# screen.net
KiCad netlist of a schematic drawn in Altium Designer
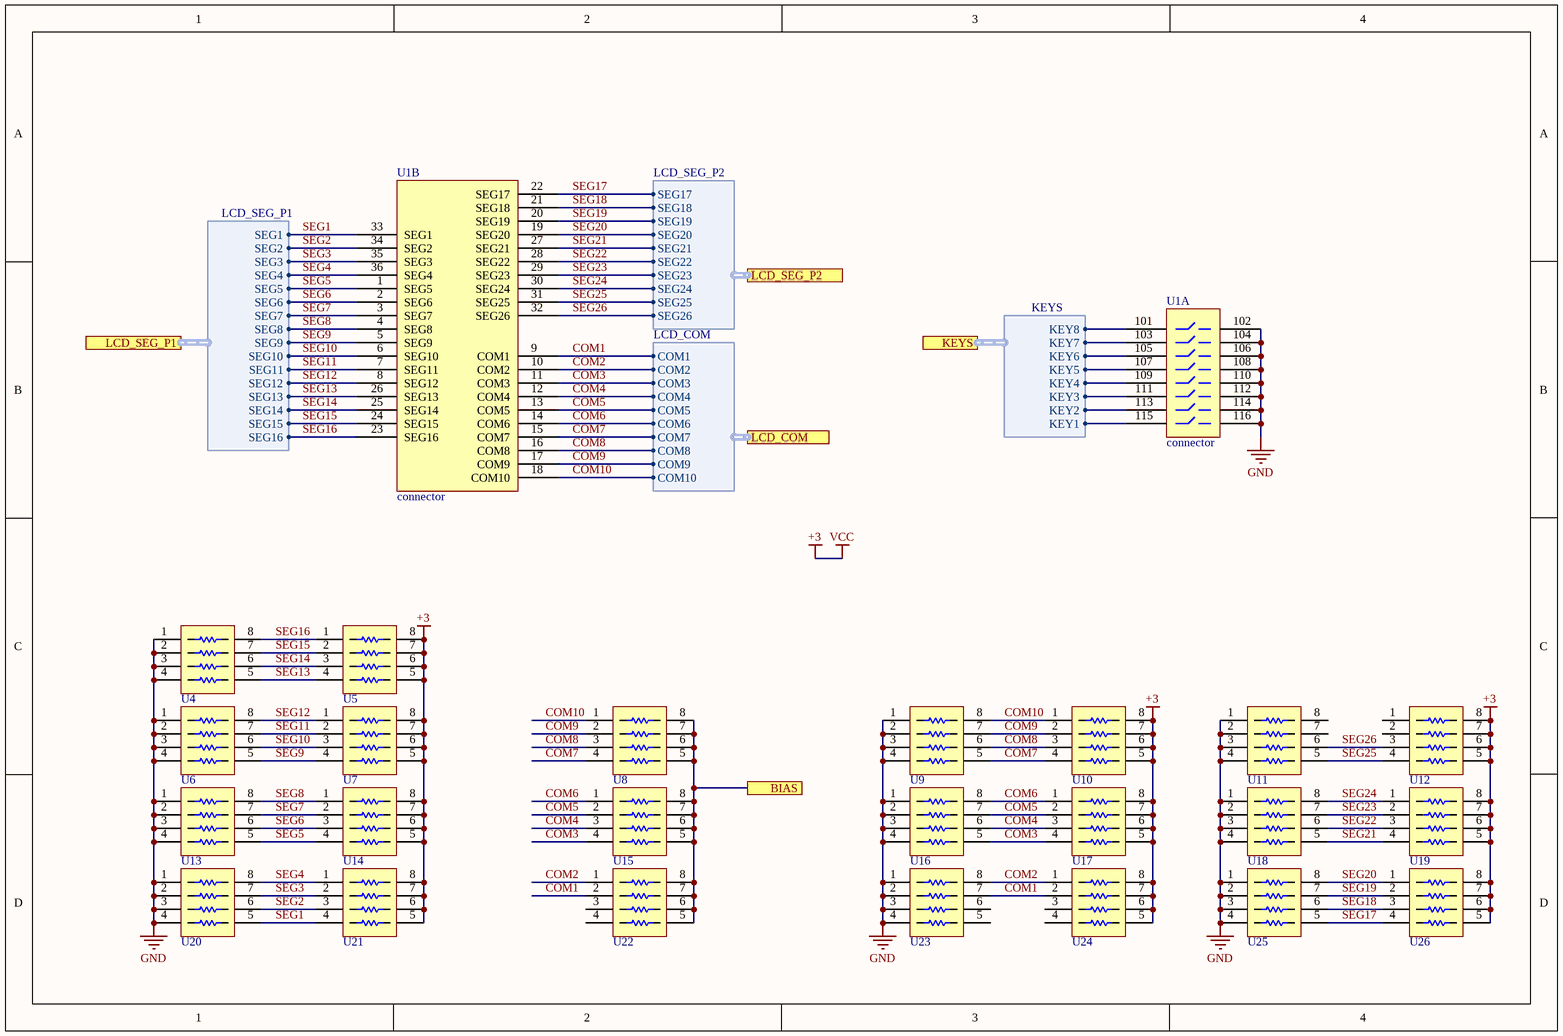
[diagram p0: screen.SchDoc]

(export (version "E")
  (design (tool "Eeschema 10.0.6"))
  (components
    (comp (ref "U1") (value "connector") (footprint "kunborad") (libsource (lib "cl_sch") (part "kunboard")))
    (comp (ref "U4")
      (value "RES_BATCH")
      (footprint "0603_RES_BATCH")
      (libsource (lib "cl_sch") (part "RES_BATCH"))
    )
    (comp (ref "U5")
      (value "RES_BATCH")
      (footprint "0603_RES_BATCH")
      (libsource (lib "cl_sch") (part "RES_BATCH"))
    )
    (comp (ref "U6")
      (value "RES_BATCH")
      (footprint "0603_RES_BATCH")
      (libsource (lib "cl_sch") (part "RES_BATCH"))
    )
    (comp (ref "U7")
      (value "RES_BATCH")
      (footprint "0603_RES_BATCH")
      (libsource (lib "cl_sch") (part "RES_BATCH"))
    )
    (comp (ref "U8")
      (value "RES_BATCH")
      (footprint "0603_RES_BATCH")
      (libsource (lib "cl_sch") (part "RES_BATCH"))
    )
    (comp (ref "U9")
      (value "RES_BATCH")
      (footprint "0603_RES_BATCH")
      (libsource (lib "cl_sch") (part "RES_BATCH"))
    )
    (comp (ref "U10")
      (value "RES_BATCH")
      (footprint "0603_RES_BATCH")
      (libsource (lib "cl_sch") (part "RES_BATCH"))
    )
    (comp (ref "U11")
      (value "RES_BATCH")
      (footprint "0603_RES_BATCH")
      (libsource (lib "cl_sch") (part "RES_BATCH"))
    )
    (comp (ref "U12")
      (value "RES_BATCH")
      (footprint "0603_RES_BATCH")
      (libsource (lib "cl_sch") (part "RES_BATCH"))
    )
    (comp (ref "U13")
      (value "RES_BATCH")
      (footprint "0603_RES_BATCH")
      (libsource (lib "cl_sch") (part "RES_BATCH"))
    )
    (comp (ref "U14")
      (value "RES_BATCH")
      (footprint "0603_RES_BATCH")
      (libsource (lib "cl_sch") (part "RES_BATCH"))
    )
    (comp (ref "U15")
      (value "RES_BATCH")
      (footprint "0603_RES_BATCH")
      (libsource (lib "cl_sch") (part "RES_BATCH"))
    )
    (comp (ref "U16")
      (value "RES_BATCH")
      (footprint "0603_RES_BATCH")
      (libsource (lib "cl_sch") (part "RES_BATCH"))
    )
    (comp (ref "U17")
      (value "RES_BATCH")
      (footprint "0603_RES_BATCH")
      (libsource (lib "cl_sch") (part "RES_BATCH"))
    )
    (comp (ref "U18")
      (value "RES_BATCH")
      (footprint "0603_RES_BATCH")
      (libsource (lib "cl_sch") (part "RES_BATCH"))
    )
    (comp (ref "U19")
      (value "RES_BATCH")
      (footprint "0603_RES_BATCH")
      (libsource (lib "cl_sch") (part "RES_BATCH"))
    )
    (comp (ref "U20")
      (value "RES_BATCH")
      (footprint "0603_RES_BATCH")
      (libsource (lib "cl_sch") (part "RES_BATCH"))
    )
    (comp (ref "U21")
      (value "RES_BATCH")
      (footprint "0603_RES_BATCH")
      (libsource (lib "cl_sch") (part "RES_BATCH"))
    )
    (comp (ref "U22")
      (value "RES_BATCH")
      (footprint "0603_RES_BATCH")
      (libsource (lib "cl_sch") (part "RES_BATCH"))
    )
    (comp (ref "U23")
      (value "RES_BATCH")
      (footprint "0603_RES_BATCH")
      (libsource (lib "cl_sch") (part "RES_BATCH"))
    )
    (comp (ref "U24")
      (value "RES_BATCH")
      (footprint "0603_RES_BATCH")
      (libsource (lib "cl_sch") (part "RES_BATCH"))
    )
    (comp (ref "U25")
      (value "RES_BATCH")
      (footprint "0603_RES_BATCH")
      (libsource (lib "cl_sch") (part "RES_BATCH"))
    )
    (comp (ref "U26")
      (value "RES_BATCH")
      (footprint "0603_RES_BATCH")
      (libsource (lib "cl_sch") (part "RES_BATCH"))
    )
  )
  (nets
    (net (code "5") (name "+3") (class "Default")
      (node (ref "U10") (pin "5") (pinfunction "5_5") (pintype "passive"))
      (node (ref "U10") (pin "6") (pinfunction "6_6") (pintype "passive"))
      (node (ref "U10") (pin "7") (pinfunction "7_7") (pintype "passive"))
      (node (ref "U10") (pin "8") (pinfunction "8_8") (pintype "passive"))
      (node (ref "U12") (pin "5") (pinfunction "5_5") (pintype "passive"))
      (node (ref "U12") (pin "6") (pinfunction "6_6") (pintype "passive"))
      (node (ref "U12") (pin "7") (pinfunction "7_7") (pintype "passive"))
      (node (ref "U12") (pin "8") (pinfunction "8_8") (pintype "passive"))
      (node (ref "U14") (pin "5") (pinfunction "5_5") (pintype "passive"))
      (node (ref "U14") (pin "6") (pinfunction "6_6") (pintype "passive"))
      (node (ref "U14") (pin "7") (pinfunction "7_7") (pintype "passive"))
      (node (ref "U14") (pin "8") (pinfunction "8_8") (pintype "passive"))
      (node (ref "U17") (pin "5") (pinfunction "5_5") (pintype "passive"))
      (node (ref "U17") (pin "6") (pinfunction "6_6") (pintype "passive"))
      (node (ref "U17") (pin "7") (pinfunction "7_7") (pintype "passive"))
      (node (ref "U17") (pin "8") (pinfunction "8_8") (pintype "passive"))
      (node (ref "U19") (pin "5") (pinfunction "5_5") (pintype "passive"))
      (node (ref "U19") (pin "6") (pinfunction "6_6") (pintype "passive"))
      (node (ref "U19") (pin "7") (pinfunction "7_7") (pintype "passive"))
      (node (ref "U19") (pin "8") (pinfunction "8_8") (pintype "passive"))
      (node (ref "U21") (pin "5") (pinfunction "5_5") (pintype "passive"))
      (node (ref "U21") (pin "6") (pinfunction "6_6") (pintype "passive"))
      (node (ref "U21") (pin "7") (pinfunction "7_7") (pintype "passive"))
      (node (ref "U21") (pin "8") (pinfunction "8_8") (pintype "passive"))
      (node (ref "U24") (pin "5") (pinfunction "5_5") (pintype "passive"))
      (node (ref "U24") (pin "6") (pinfunction "6_6") (pintype "passive"))
      (node (ref "U24") (pin "7") (pinfunction "7_7") (pintype "passive"))
      (node (ref "U24") (pin "8") (pinfunction "8_8") (pintype "passive"))
      (node (ref "U26") (pin "5") (pinfunction "5_5") (pintype "passive"))
      (node (ref "U26") (pin "6") (pinfunction "6_6") (pintype "passive"))
      (node (ref "U26") (pin "7") (pinfunction "7_7") (pintype "passive"))
      (node (ref "U26") (pin "8") (pinfunction "8_8") (pintype "passive"))
      (node (ref "U5") (pin "5") (pinfunction "5_5") (pintype "passive"))
      (node (ref "U5") (pin "6") (pinfunction "6_6") (pintype "passive"))
      (node (ref "U5") (pin "7") (pinfunction "7_7") (pintype "passive"))
      (node (ref "U5") (pin "8") (pinfunction "8_8") (pintype "passive"))
      (node (ref "U7") (pin "5") (pinfunction "5_5") (pintype "passive"))
      (node (ref "U7") (pin "6") (pinfunction "6_6") (pintype "passive"))
      (node (ref "U7") (pin "7") (pinfunction "7_7") (pintype "passive"))
      (node (ref "U7") (pin "8") (pinfunction "8_8") (pintype "passive"))
    )
    (net (code "6") (name "/BIAS") (class "Default")
      (node (ref "U15") (pin "5") (pinfunction "5_5") (pintype "passive"))
      (node (ref "U15") (pin "6") (pinfunction "6_6") (pintype "passive"))
      (node (ref "U15") (pin "7") (pinfunction "7_7") (pintype "passive"))
      (node (ref "U15") (pin "8") (pinfunction "8_8") (pintype "passive"))
      (node (ref "U22") (pin "5") (pinfunction "5_5") (pintype "passive"))
      (node (ref "U22") (pin "6") (pinfunction "6_6") (pintype "passive"))
      (node (ref "U22") (pin "7") (pinfunction "7_7") (pintype "passive"))
      (node (ref "U22") (pin "8") (pinfunction "8_8") (pintype "passive"))
      (node (ref "U8") (pin "5") (pinfunction "5_5") (pintype "passive"))
      (node (ref "U8") (pin "6") (pinfunction "6_6") (pintype "passive"))
      (node (ref "U8") (pin "7") (pinfunction "7_7") (pintype "passive"))
      (node (ref "U8") (pin "8") (pinfunction "8_8") (pintype "passive"))
    )
    (net (code "7") (name "/COM1") (class "Default")
      (node (ref "U1") (pin "9") (pinfunction "COM1_9") (pintype "passive"))
      (node (ref "U22") (pin "2") (pinfunction "2_2") (pintype "passive"))
      (node (ref "U23") (pin "7") (pinfunction "7_7") (pintype "passive"))
      (node (ref "U24") (pin "2") (pinfunction "2_2") (pintype "passive"))
    )
    (net (code "8") (name "/COM2") (class "Default")
      (node (ref "U1") (pin "10") (pinfunction "COM2_10") (pintype "passive"))
      (node (ref "U22") (pin "1") (pinfunction "1_1") (pintype "passive"))
      (node (ref "U23") (pin "8") (pinfunction "8_8") (pintype "passive"))
      (node (ref "U24") (pin "1") (pinfunction "1_1") (pintype "passive"))
    )
    (net (code "9") (name "/COM3") (class "Default")
      (node (ref "U1") (pin "11") (pinfunction "COM3_11") (pintype "passive"))
      (node (ref "U15") (pin "4") (pinfunction "4_4") (pintype "passive"))
      (node (ref "U16") (pin "5") (pinfunction "5_5") (pintype "passive"))
      (node (ref "U17") (pin "4") (pinfunction "4_4") (pintype "passive"))
    )
    (net (code "10") (name "/COM4") (class "Default")
      (node (ref "U1") (pin "12") (pinfunction "COM4_12") (pintype "passive"))
      (node (ref "U15") (pin "3") (pinfunction "3_3") (pintype "passive"))
      (node (ref "U16") (pin "6") (pinfunction "6_6") (pintype "passive"))
      (node (ref "U17") (pin "3") (pinfunction "3_3") (pintype "passive"))
    )
    (net (code "11") (name "/COM5") (class "Default")
      (node (ref "U1") (pin "13") (pinfunction "COM5_13") (pintype "passive"))
      (node (ref "U15") (pin "2") (pinfunction "2_2") (pintype "passive"))
      (node (ref "U16") (pin "7") (pinfunction "7_7") (pintype "passive"))
      (node (ref "U17") (pin "2") (pinfunction "2_2") (pintype "passive"))
    )
    (net (code "12") (name "/COM6") (class "Default")
      (node (ref "U1") (pin "14") (pinfunction "COM6_14") (pintype "passive"))
      (node (ref "U15") (pin "1") (pinfunction "1_1") (pintype "passive"))
      (node (ref "U16") (pin "8") (pinfunction "8_8") (pintype "passive"))
      (node (ref "U17") (pin "1") (pinfunction "1_1") (pintype "passive"))
    )
    (net (code "13") (name "/COM7") (class "Default")
      (node (ref "U1") (pin "15") (pinfunction "COM7_15") (pintype "passive"))
      (node (ref "U10") (pin "4") (pinfunction "4_4") (pintype "passive"))
      (node (ref "U8") (pin "4") (pinfunction "4_4") (pintype "passive"))
      (node (ref "U9") (pin "5") (pinfunction "5_5") (pintype "passive"))
    )
    (net (code "14") (name "/COM8") (class "Default")
      (node (ref "U1") (pin "16") (pinfunction "COM8_16") (pintype "passive"))
      (node (ref "U10") (pin "3") (pinfunction "3_3") (pintype "passive"))
      (node (ref "U8") (pin "3") (pinfunction "3_3") (pintype "passive"))
      (node (ref "U9") (pin "6") (pinfunction "6_6") (pintype "passive"))
    )
    (net (code "15") (name "/COM9") (class "Default")
      (node (ref "U1") (pin "17") (pinfunction "COM9_17") (pintype "passive"))
      (node (ref "U10") (pin "2") (pinfunction "2_2") (pintype "passive"))
      (node (ref "U8") (pin "2") (pinfunction "2_2") (pintype "passive"))
      (node (ref "U9") (pin "7") (pinfunction "7_7") (pintype "passive"))
    )
    (net (code "16") (name "/COM10") (class "Default")
      (node (ref "U1") (pin "18") (pinfunction "COM10_18") (pintype "passive"))
      (node (ref "U10") (pin "1") (pinfunction "1_1") (pintype "passive"))
      (node (ref "U8") (pin "1") (pinfunction "1_1") (pintype "passive"))
      (node (ref "U9") (pin "8") (pinfunction "8_8") (pintype "passive"))
    )
    (net (code "17") (name "/KEY1") (class "Default")
      (node (ref "U1") (pin "115") (pinfunction "115_115") (pintype "passive"))
    )
    (net (code "18") (name "/KEY2") (class "Default")
      (node (ref "U1") (pin "113") (pinfunction "113_113") (pintype "passive"))
    )
    (net (code "19") (name "/KEY3") (class "Default")
      (node (ref "U1") (pin "111") (pinfunction "111_111") (pintype "passive"))
    )
    (net (code "20") (name "/KEY4") (class "Default")
      (node (ref "U1") (pin "109") (pinfunction "109_109") (pintype "passive"))
    )
    (net (code "21") (name "/KEY5") (class "Default")
      (node (ref "U1") (pin "107") (pinfunction "107_107") (pintype "passive"))
    )
    (net (code "22") (name "/KEY6") (class "Default")
      (node (ref "U1") (pin "105") (pinfunction "105_105") (pintype "passive"))
    )
    (net (code "23") (name "/KEY7") (class "Default")
      (node (ref "U1") (pin "103") (pinfunction "103_103") (pintype "passive"))
    )
    (net (code "24") (name "/KEY8") (class "Default")
      (node (ref "U1") (pin "101") (pinfunction "11_101") (pintype "passive"))
    )
    (net (code "25") (name "/SEG1") (class "Default")
      (node (ref "U1") (pin "33") (pinfunction "SEG1_33") (pintype "passive"))
      (node (ref "U20") (pin "5") (pinfunction "5_5") (pintype "passive"))
      (node (ref "U21") (pin "4") (pinfunction "4_4") (pintype "passive"))
    )
    (net (code "26") (name "/SEG2") (class "Default")
      (node (ref "U1") (pin "34") (pinfunction "SEG2_34") (pintype "passive"))
      (node (ref "U20") (pin "6") (pinfunction "6_6") (pintype "passive"))
      (node (ref "U21") (pin "3") (pinfunction "3_3") (pintype "passive"))
    )
    (net (code "27") (name "/SEG3") (class "Default")
      (node (ref "U1") (pin "35") (pinfunction "SEG3_35") (pintype "passive"))
      (node (ref "U20") (pin "7") (pinfunction "7_7") (pintype "passive"))
      (node (ref "U21") (pin "2") (pinfunction "2_2") (pintype "passive"))
    )
    (net (code "28") (name "/SEG4") (class "Default")
      (node (ref "U1") (pin "36") (pinfunction "SEG4_36") (pintype "passive"))
      (node (ref "U20") (pin "8") (pinfunction "8_8") (pintype "passive"))
      (node (ref "U21") (pin "1") (pinfunction "1_1") (pintype "passive"))
    )
    (net (code "29") (name "/SEG5") (class "Default")
      (node (ref "U1") (pin "1") (pinfunction "SEG5_1") (pintype "passive"))
      (node (ref "U13") (pin "5") (pinfunction "5_5") (pintype "passive"))
      (node (ref "U14") (pin "4") (pinfunction "4_4") (pintype "passive"))
    )
    (net (code "30") (name "/SEG6") (class "Default")
      (node (ref "U1") (pin "2") (pinfunction "SEG6_2") (pintype "passive"))
      (node (ref "U13") (pin "6") (pinfunction "6_6") (pintype "passive"))
      (node (ref "U14") (pin "3") (pinfunction "3_3") (pintype "passive"))
    )
    (net (code "31") (name "/SEG7") (class "Default")
      (node (ref "U1") (pin "3") (pinfunction "SEG7_3") (pintype "passive"))
      (node (ref "U13") (pin "7") (pinfunction "7_7") (pintype "passive"))
      (node (ref "U14") (pin "2") (pinfunction "2_2") (pintype "passive"))
    )
    (net (code "32") (name "/SEG8") (class "Default")
      (node (ref "U1") (pin "4") (pinfunction "SEG8_4") (pintype "passive"))
      (node (ref "U13") (pin "8") (pinfunction "8_8") (pintype "passive"))
      (node (ref "U14") (pin "1") (pinfunction "1_1") (pintype "passive"))
    )
    (net (code "33") (name "/SEG9") (class "Default")
      (node (ref "U1") (pin "5") (pinfunction "SEG9_5") (pintype "passive"))
      (node (ref "U6") (pin "5") (pinfunction "5_5") (pintype "passive"))
      (node (ref "U7") (pin "4") (pinfunction "4_4") (pintype "passive"))
    )
    (net (code "34") (name "/SEG10") (class "Default")
      (node (ref "U1") (pin "6") (pinfunction "SEG10_6") (pintype "passive"))
      (node (ref "U6") (pin "6") (pinfunction "6_6") (pintype "passive"))
      (node (ref "U7") (pin "3") (pinfunction "3_3") (pintype "passive"))
    )
    (net (code "35") (name "/SEG11") (class "Default")
      (node (ref "U1") (pin "7") (pinfunction "SEG11_7") (pintype "passive"))
      (node (ref "U6") (pin "7") (pinfunction "7_7") (pintype "passive"))
      (node (ref "U7") (pin "2") (pinfunction "2_2") (pintype "passive"))
    )
    (net (code "36") (name "/SEG12") (class "Default")
      (node (ref "U1") (pin "8") (pinfunction "SEG12_8") (pintype "passive"))
      (node (ref "U6") (pin "8") (pinfunction "8_8") (pintype "passive"))
      (node (ref "U7") (pin "1") (pinfunction "1_1") (pintype "passive"))
    )
    (net (code "37") (name "/SEG13") (class "Default")
      (node (ref "U1") (pin "26") (pinfunction "SEG13_26") (pintype "passive"))
      (node (ref "U4") (pin "5") (pinfunction "5_5") (pintype "passive"))
      (node (ref "U5") (pin "4") (pinfunction "4_4") (pintype "passive"))
    )
    (net (code "38") (name "/SEG14") (class "Default")
      (node (ref "U1") (pin "25") (pinfunction "SEG14_25") (pintype "passive"))
      (node (ref "U4") (pin "6") (pinfunction "6_6") (pintype "passive"))
      (node (ref "U5") (pin "3") (pinfunction "3_3") (pintype "passive"))
    )
    (net (code "39") (name "/SEG15") (class "Default")
      (node (ref "U1") (pin "24") (pinfunction "SEG15_24") (pintype "passive"))
      (node (ref "U4") (pin "7") (pinfunction "7_7") (pintype "passive"))
      (node (ref "U5") (pin "2") (pinfunction "2_2") (pintype "passive"))
    )
    (net (code "40") (name "/SEG16") (class "Default")
      (node (ref "U1") (pin "23") (pinfunction "SEG16_23") (pintype "passive"))
      (node (ref "U4") (pin "8") (pinfunction "8_8") (pintype "passive"))
      (node (ref "U5") (pin "1") (pinfunction "1_1") (pintype "passive"))
    )
    (net (code "41") (name "/SEG17") (class "Default")
      (node (ref "U1") (pin "22") (pinfunction "SEG17_22") (pintype "passive"))
      (node (ref "U25") (pin "5") (pinfunction "5_5") (pintype "passive"))
      (node (ref "U26") (pin "4") (pinfunction "4_4") (pintype "passive"))
    )
    (net (code "42") (name "/SEG18") (class "Default")
      (node (ref "U1") (pin "21") (pinfunction "SEG18_21") (pintype "passive"))
      (node (ref "U25") (pin "6") (pinfunction "6_6") (pintype "passive"))
      (node (ref "U26") (pin "3") (pinfunction "3_3") (pintype "passive"))
    )
    (net (code "43") (name "/SEG19") (class "Default")
      (node (ref "U1") (pin "20") (pinfunction "SEG19_20") (pintype "passive"))
      (node (ref "U25") (pin "7") (pinfunction "7_7") (pintype "passive"))
      (node (ref "U26") (pin "2") (pinfunction "2_2") (pintype "passive"))
    )
    (net (code "44") (name "/SEG20") (class "Default")
      (node (ref "U1") (pin "19") (pinfunction "SEG20_19") (pintype "passive"))
      (node (ref "U25") (pin "8") (pinfunction "8_8") (pintype "passive"))
      (node (ref "U26") (pin "1") (pinfunction "1_1") (pintype "passive"))
    )
    (net (code "45") (name "/SEG21") (class "Default")
      (node (ref "U1") (pin "27") (pinfunction "SEG21_27") (pintype "passive"))
      (node (ref "U18") (pin "5") (pinfunction "5_5") (pintype "passive"))
      (node (ref "U19") (pin "4") (pinfunction "4_4") (pintype "passive"))
    )
    (net (code "46") (name "/SEG22") (class "Default")
      (node (ref "U1") (pin "28") (pinfunction "SEG22_28") (pintype "passive"))
      (node (ref "U18") (pin "6") (pinfunction "6_6") (pintype "passive"))
      (node (ref "U19") (pin "3") (pinfunction "3_3") (pintype "passive"))
    )
    (net (code "47") (name "/SEG23") (class "Default")
      (node (ref "U1") (pin "29") (pinfunction "SEG23_29") (pintype "passive"))
      (node (ref "U18") (pin "7") (pinfunction "7_7") (pintype "passive"))
      (node (ref "U19") (pin "2") (pinfunction "2_2") (pintype "passive"))
    )
    (net (code "48") (name "/SEG24") (class "Default")
      (node (ref "U1") (pin "30") (pinfunction "SEG24_30") (pintype "passive"))
      (node (ref "U18") (pin "8") (pinfunction "8_8") (pintype "passive"))
      (node (ref "U19") (pin "1") (pinfunction "1_1") (pintype "passive"))
    )
    (net (code "49") (name "/SEG25") (class "Default")
      (node (ref "U1") (pin "31") (pinfunction "SEG25_31") (pintype "passive"))
      (node (ref "U11") (pin "5") (pinfunction "5_5") (pintype "passive"))
      (node (ref "U12") (pin "4") (pinfunction "4_4") (pintype "passive"))
    )
    (net (code "50") (name "/SEG26") (class "Default")
      (node (ref "U1") (pin "32") (pinfunction "SEG26_32") (pintype "passive"))
      (node (ref "U11") (pin "6") (pinfunction "6_6") (pintype "passive"))
      (node (ref "U12") (pin "3") (pinfunction "3_3") (pintype "passive"))
    )
    (net (code "55") (name "GND") (class "Default")
      (node (ref "U1") (pin "102") (pinfunction "12_102") (pintype "passive"))
      (node (ref "U1") (pin "104") (pinfunction "104_104") (pintype "passive"))
      (node (ref "U1") (pin "106") (pinfunction "106_106") (pintype "passive"))
      (node (ref "U1") (pin "108") (pinfunction "108_108") (pintype "passive"))
      (node (ref "U1") (pin "110") (pinfunction "110_110") (pintype "passive"))
      (node (ref "U1") (pin "112") (pinfunction "112_112") (pintype "passive"))
      (node (ref "U1") (pin "114") (pinfunction "114_114") (pintype "passive"))
      (node (ref "U1") (pin "116") (pinfunction "116_116") (pintype "passive"))
      (node (ref "U11") (pin "1") (pinfunction "1_1") (pintype "passive"))
      (node (ref "U11") (pin "2") (pinfunction "2_2") (pintype "passive"))
      (node (ref "U11") (pin "3") (pinfunction "3_3") (pintype "passive"))
      (node (ref "U11") (pin "4") (pinfunction "4_4") (pintype "passive"))
      (node (ref "U13") (pin "1") (pinfunction "1_1") (pintype "passive"))
      (node (ref "U13") (pin "2") (pinfunction "2_2") (pintype "passive"))
      (node (ref "U13") (pin "3") (pinfunction "3_3") (pintype "passive"))
      (node (ref "U13") (pin "4") (pinfunction "4_4") (pintype "passive"))
      (node (ref "U16") (pin "1") (pinfunction "1_1") (pintype "passive"))
      (node (ref "U16") (pin "2") (pinfunction "2_2") (pintype "passive"))
      (node (ref "U16") (pin "3") (pinfunction "3_3") (pintype "passive"))
      (node (ref "U16") (pin "4") (pinfunction "4_4") (pintype "passive"))
      (node (ref "U18") (pin "1") (pinfunction "1_1") (pintype "passive"))
      (node (ref "U18") (pin "2") (pinfunction "2_2") (pintype "passive"))
      (node (ref "U18") (pin "3") (pinfunction "3_3") (pintype "passive"))
      (node (ref "U18") (pin "4") (pinfunction "4_4") (pintype "passive"))
      (node (ref "U20") (pin "1") (pinfunction "1_1") (pintype "passive"))
      (node (ref "U20") (pin "2") (pinfunction "2_2") (pintype "passive"))
      (node (ref "U20") (pin "3") (pinfunction "3_3") (pintype "passive"))
      (node (ref "U20") (pin "4") (pinfunction "4_4") (pintype "passive"))
      (node (ref "U23") (pin "1") (pinfunction "1_1") (pintype "passive"))
      (node (ref "U23") (pin "2") (pinfunction "2_2") (pintype "passive"))
      (node (ref "U23") (pin "3") (pinfunction "3_3") (pintype "passive"))
      (node (ref "U23") (pin "4") (pinfunction "4_4") (pintype "passive"))
      (node (ref "U25") (pin "1") (pinfunction "1_1") (pintype "passive"))
      (node (ref "U25") (pin "2") (pinfunction "2_2") (pintype "passive"))
      (node (ref "U25") (pin "3") (pinfunction "3_3") (pintype "passive"))
      (node (ref "U25") (pin "4") (pinfunction "4_4") (pintype "passive"))
      (node (ref "U4") (pin "1") (pinfunction "1_1") (pintype "passive"))
      (node (ref "U4") (pin "2") (pinfunction "2_2") (pintype "passive"))
      (node (ref "U4") (pin "3") (pinfunction "3_3") (pintype "passive"))
      (node (ref "U4") (pin "4") (pinfunction "4_4") (pintype "passive"))
      (node (ref "U6") (pin "1") (pinfunction "1_1") (pintype "passive"))
      (node (ref "U6") (pin "2") (pinfunction "2_2") (pintype "passive"))
      (node (ref "U6") (pin "3") (pinfunction "3_3") (pintype "passive"))
      (node (ref "U6") (pin "4") (pinfunction "4_4") (pintype "passive"))
      (node (ref "U9") (pin "1") (pinfunction "1_1") (pintype "passive"))
      (node (ref "U9") (pin "2") (pinfunction "2_2") (pintype "passive"))
      (node (ref "U9") (pin "3") (pinfunction "3_3") (pintype "passive"))
      (node (ref "U9") (pin "4") (pinfunction "4_4") (pintype "passive"))
    )
    (net (code "56") (name "unconnected-(U11-Pad7)") (class "Default")
      (node (ref "U11") (pin "7") (pinfunction "7_7") (pintype "passive"))
    )
    (net (code "57") (name "unconnected-(U11-Pad8)") (class "Default")
      (node (ref "U11") (pin "8") (pinfunction "8_8") (pintype "passive"))
    )
    (net (code "58") (name "unconnected-(U12-Pad1)") (class "Default")
      (node (ref "U12") (pin "1") (pinfunction "1_1") (pintype "passive"))
    )
    (net (code "59") (name "unconnected-(U12-Pad2)") (class "Default")
      (node (ref "U12") (pin "2") (pinfunction "2_2") (pintype "passive"))
    )
    (net (code "60") (name "unconnected-(U22-Pad3)") (class "Default")
      (node (ref "U22") (pin "3") (pinfunction "3_3") (pintype "passive"))
    )
    (net (code "61") (name "unconnected-(U22-Pad4)") (class "Default")
      (node (ref "U22") (pin "4") (pinfunction "4_4") (pintype "passive"))
    )
    (net (code "62") (name "unconnected-(U23-Pad5)") (class "Default")
      (node (ref "U23") (pin "5") (pinfunction "5_5") (pintype "passive"))
    )
    (net (code "63") (name "unconnected-(U23-Pad6)") (class "Default")
      (node (ref "U23") (pin "6") (pinfunction "6_6") (pintype "passive"))
    )
    (net (code "64") (name "unconnected-(U24-Pad3)") (class "Default")
      (node (ref "U24") (pin "3") (pinfunction "3_3") (pintype "passive"))
    )
    (net (code "65") (name "unconnected-(U24-Pad4)") (class "Default")
      (node (ref "U24") (pin "4") (pinfunction "4_4") (pintype "passive"))
    )
  )
)
